# BMS-Shield_rev3.net
KiCad netlist of a schematic drawn in EAGLE
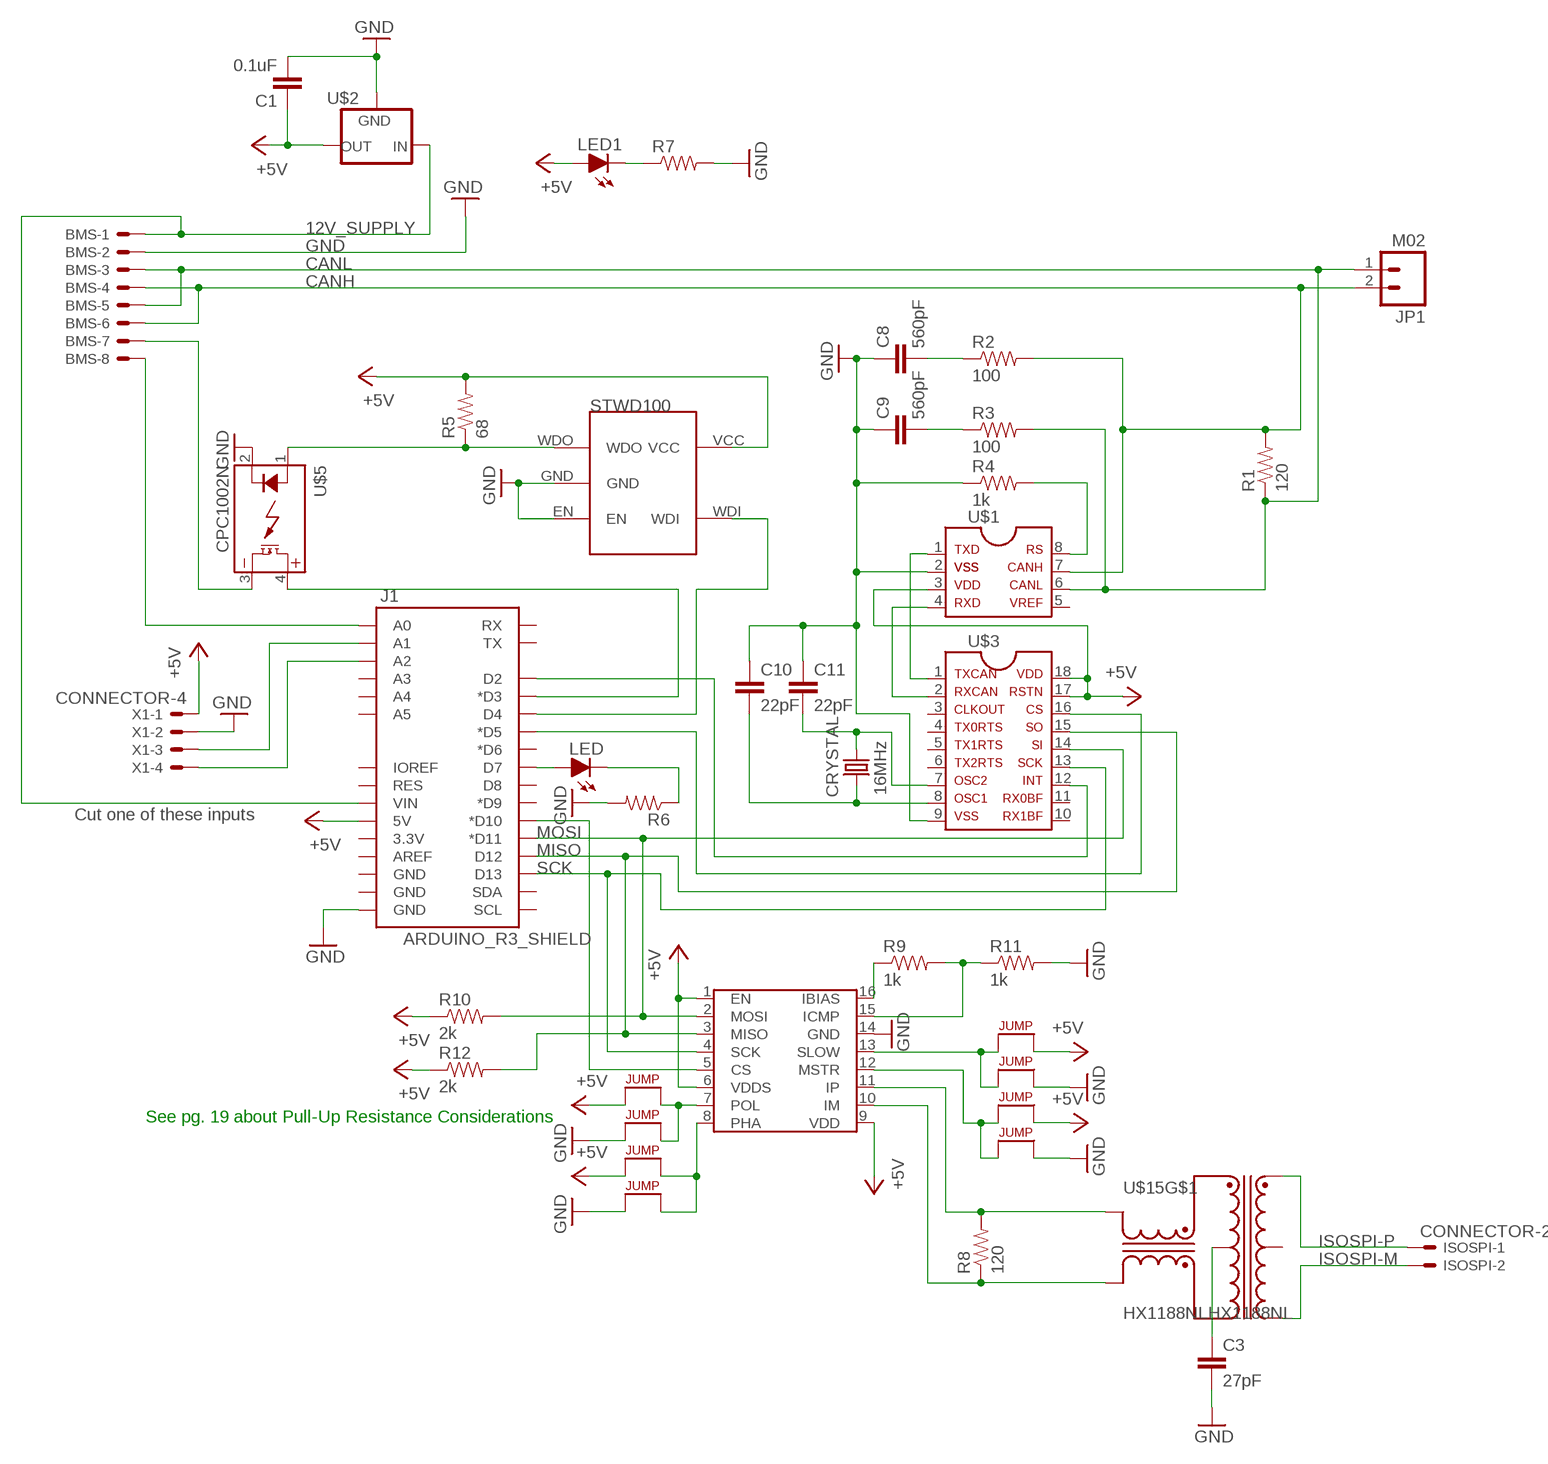
[diagram p0: schematic, sheet 1]

(export (version "E")
  (design (tool "Eeschema 10.0.6"))
  (components
    (comp (ref "BMS")
      (value "MINIFIT_5566-8")
      (footprint "eagle-import:MINIFIT_5566-8")
      (libsource (lib "eagle-import") (part "MINIFIT_5566-8"))
    )
    (comp (ref "C1")
      (value "0.1uF")
      (footprint "eagle-import:0805")
      (libsource (lib "eagle-import") (part "CAP0805"))
    )
    (comp (ref "C3")
      (value "27pF")
      (footprint "eagle-import:0805")
      (libsource (lib "eagle-import") (part "CAP0805"))
    )
    (comp (ref "C8")
      (value "560pF")
      (footprint "eagle-import:0805")
      (libsource (lib "eagle-import") (part "CAP0805"))
    )
    (comp (ref "C9")
      (value "560pF")
      (footprint "eagle-import:0805")
      (libsource (lib "eagle-import") (part "CAP0805"))
    )
    (comp (ref "C10")
      (value "22pF")
      (footprint "eagle-import:0805")
      (libsource (lib "eagle-import") (part "CAP0805"))
    )
    (comp (ref "C11")
      (value "22pF")
      (footprint "eagle-import:0805")
      (libsource (lib "eagle-import") (part "CAP0805"))
    )
    (comp (ref "CRYSTAL")
      (value "16MHz")
      (footprint "eagle-import:HC49UP")
      (libsource (lib "eagle-import") (part "CRYSTALSMD"))
    )
    (comp (ref "ISOSPI")
      (value "CONNECTOR-2")
      (footprint "eagle-import:MINIFIT_5566-2")
      (libsource (lib "eagle-import") (part "CONNECTOR-2"))
    )
    (comp (ref "J1")
      (value "ARDUINO_R3_SHIELD")
      (footprint "eagle-import:UNO_R3_SHIELD")
      (libsource (lib "eagle-import") (part "ARDUINO_R3_SHIELD"))
    )
    (comp (ref "JP1")
      (value "M02")
      (footprint "eagle-import:1X02")
      (libsource (lib "eagle-import") (part "M02"))
    )
    (comp (ref "LED")
      (value "LED-0805")
      (footprint "eagle-import:LED-805")
      (libsource (lib "eagle-import") (part "LED-0805"))
    )
    (comp (ref "LED1")
      (value "LED-0805")
      (footprint "eagle-import:LED-805")
      (libsource (lib "eagle-import") (part "LED-0805"))
    )
    (comp (ref "R1")
      (value "120")
      (footprint "eagle-import:0805")
      (libsource (lib "eagle-import") (part "RESISTOR0805-RES"))
    )
    (comp (ref "R2")
      (value "100")
      (footprint "eagle-import:0805")
      (libsource (lib "eagle-import") (part "RESISTOR0805-RES"))
    )
    (comp (ref "R3")
      (value "100")
      (footprint "eagle-import:0805")
      (libsource (lib "eagle-import") (part "RESISTOR0805-RES"))
    )
    (comp (ref "R4")
      (value "1k")
      (footprint "eagle-import:0805")
      (libsource (lib "eagle-import") (part "RESISTOR0805-RES"))
    )
    (comp (ref "R5")
      (value "68")
      (footprint "eagle-import:0805")
      (libsource (lib "eagle-import") (part "RESISTOR0805-RES"))
    )
    (comp (ref "R6")
      (value "RESISTOR0805-RES")
      (footprint "eagle-import:0805")
      (libsource (lib "eagle-import") (part "RESISTOR0805-RES"))
    )
    (comp (ref "R7")
      (value "RESISTOR0805-RES")
      (footprint "eagle-import:0805")
      (libsource (lib "eagle-import") (part "RESISTOR0805-RES"))
    )
    (comp (ref "R8")
      (value "120")
      (footprint "eagle-import:0805")
      (libsource (lib "eagle-import") (part "RESISTOR0805-RES"))
    )
    (comp (ref "R9")
      (value "1k")
      (footprint "eagle-import:0805")
      (libsource (lib "eagle-import") (part "RESISTOR0805-RES"))
    )
    (comp (ref "R10")
      (value "2k")
      (footprint "eagle-import:0805")
      (libsource (lib "eagle-import") (part "RESISTOR0805-RES"))
    )
    (comp (ref "R11")
      (value "1k")
      (footprint "eagle-import:0805")
      (libsource (lib "eagle-import") (part "RESISTOR0805-RES"))
    )
    (comp (ref "R12")
      (value "2k")
      (footprint "eagle-import:0805")
      (libsource (lib "eagle-import") (part "RESISTOR0805-RES"))
    )
    (comp (ref "U$1")
      (value "MCP2551")
      (footprint "eagle-import:SOIC-08")
      (libsource (lib "eagle-import") (part "MCP2551"))
    )
    (comp (ref "U$2")
      (value "5VREG_LM340-NLM340MPX-5.0/NOPB")
      (footprint "eagle-import:SOT223")
      (libsource (lib "eagle-import") (part "5VREG_LM340-NLM340MPX-5.0/NOPB"))
    )
    (comp (ref "U$3")
      (value "MCP2515SMD")
      (footprint "eagle-import:SOIC-18W")
      (libsource (lib "eagle-import") (part "MCP2515SMD"))
    )
    (comp (ref "U$4")
      (value "STWD100")
      (footprint "eagle-import:SOT23-5")
      (libsource (lib "eagle-import") (part "STWD100"))
    )
    (comp (ref "U$5")
      (value "CPC1002N")
      (footprint "eagle-import:SOP04")
      (libsource (lib "eagle-import") (part "CPC1002N"))
    )
    (comp (ref "U$6")
      (value "LTC6820")
      (footprint "eagle-import:MSOP-16")
      (libsource (lib "eagle-import") (part "LTC6820"))
    )
    (comp (ref "U$7")
      (value "JUMPER")
      (footprint "eagle-import:0805")
      (libsource (lib "eagle-import") (part "JUMPER"))
    )
    (comp (ref "U$8")
      (value "JUMPER")
      (footprint "eagle-import:0805")
      (libsource (lib "eagle-import") (part "JUMPER"))
    )
    (comp (ref "U$9")
      (value "JUMPER")
      (footprint "eagle-import:0805")
      (libsource (lib "eagle-import") (part "JUMPER"))
    )
    (comp (ref "U$10")
      (value "JUMPER")
      (footprint "eagle-import:0805")
      (libsource (lib "eagle-import") (part "JUMPER"))
    )
    (comp (ref "U$11")
      (value "JUMPER")
      (footprint "eagle-import:0805")
      (libsource (lib "eagle-import") (part "JUMPER"))
    )
    (comp (ref "U$12")
      (value "JUMPER")
      (footprint "eagle-import:0805")
      (libsource (lib "eagle-import") (part "JUMPER"))
    )
    (comp (ref "U$13")
      (value "JUMPER")
      (footprint "eagle-import:0805")
      (libsource (lib "eagle-import") (part "JUMPER"))
    )
    (comp (ref "U$14")
      (value "JUMPER")
      (footprint "eagle-import:0805")
      (libsource (lib "eagle-import") (part "JUMPER"))
    )
    (comp (ref "U$15")
      (value "HX1188NLHX1188NL")
      (footprint "eagle-import:HX1188NL")
      (libsource (lib "eagle-import") (part "HX1188NLHX1188NL"))
    )
    (comp (ref "X1")
      (value "CONNECTOR-4")
      (footprint "eagle-import:MINIFIT_5566-4")
      (libsource (lib "eagle-import") (part "CONNECTOR-4"))
    )
  )
  (nets
    (net (code "1") (name "+5V") (class "Default")
      (node (ref "C1") (pin "1") (pinfunction "1_1") (pintype "passive"))
      (node (ref "J1") (pin "5V") (pinfunction "5V_5V") (pintype "bidirectional"))
      (node (ref "LED1") (pin "A") (pinfunction "A_A") (pintype "passive"))
      (node (ref "R10") (pin "1") (pinfunction "1_1") (pintype "passive"))
      (node (ref "R12") (pin "1") (pinfunction "1_1") (pintype "passive"))
      (node (ref "R5") (pin "2") (pinfunction "2_2") (pintype "passive"))
      (node (ref "U$1") (pin "3") (pinfunction "3_3") (pintype "passive"))
      (node (ref "U$10") (pin "1") (pinfunction "P$1_1") (pintype "bidirectional"))
      (node (ref "U$11") (pin "2") (pinfunction "P$2_2") (pintype "bidirectional"))
      (node (ref "U$13") (pin "2") (pinfunction "P$2_2") (pintype "bidirectional"))
      (node (ref "U$2") (pin "3") (pinfunction "OUT_3") (pintype "output"))
      (node (ref "U$3") (pin "17") (pinfunction "17_17") (pintype "passive"))
      (node (ref "U$3") (pin "18") (pinfunction "18_18") (pintype "passive"))
      (node (ref "U$4") (pin "VCC") (pinfunction "VCC_VCC") (pintype "bidirectional"))
      (node (ref "U$6") (pin "1") (pinfunction "EN_1") (pintype "bidirectional"))
      (node (ref "U$6") (pin "6") (pinfunction "VDDS_6") (pintype "bidirectional"))
      (node (ref "U$6") (pin "9") (pinfunction "VDD_9") (pintype "bidirectional"))
      (node (ref "U$7") (pin "1") (pinfunction "P$1_1") (pintype "bidirectional"))
      (node (ref "X1") (pin "1") (pinfunction "S_1") (pintype "passive"))
    )
    (net (code "2") (name "/12V_SUPPLY") (class "Default")
      (node (ref "BMS") (pin "1") (pinfunction "S_1") (pintype "passive"))
      (node (ref "J1") (pin "VIN") (pinfunction "VIN_VIN") (pintype "bidirectional"))
      (node (ref "U$2") (pin "1") (pinfunction "IN_1") (pintype "input"))
    )
    (net (code "3") (name "/CANH") (class "Default")
      (node (ref "BMS") (pin "4") (pinfunction "S_4") (pintype "passive"))
      (node (ref "BMS") (pin "6") (pinfunction "S_6") (pintype "passive"))
      (node (ref "JP1") (pin "2") (pinfunction "2_2") (pintype "passive"))
      (node (ref "R1") (pin "2") (pinfunction "2_2") (pintype "passive"))
      (node (ref "R2") (pin "2") (pinfunction "2_2") (pintype "passive"))
      (node (ref "U$1") (pin "7") (pinfunction "7_7") (pintype "passive"))
    )
    (net (code "4") (name "/CANL") (class "Default")
      (node (ref "BMS") (pin "3") (pinfunction "S_3") (pintype "passive"))
      (node (ref "BMS") (pin "5") (pinfunction "S_5") (pintype "passive"))
      (node (ref "JP1") (pin "1") (pinfunction "1_1") (pintype "passive"))
      (node (ref "R1") (pin "1") (pinfunction "1_1") (pintype "passive"))
      (node (ref "R3") (pin "2") (pinfunction "2_2") (pintype "passive"))
      (node (ref "U$1") (pin "6") (pinfunction "6_6") (pintype "passive"))
    )
    (net (code "5") (name "/ISOSPI-M") (class "Default")
      (node (ref "ISOSPI") (pin "2") (pinfunction "S_2") (pintype "passive"))
      (node (ref "U$15") (pin "3") (pinfunction "D-_3") (pintype "passive"))
    )
    (net (code "6") (name "/ISOSPI-P") (class "Default")
      (node (ref "ISOSPI") (pin "1") (pinfunction "S_1") (pintype "passive"))
      (node (ref "U$15") (pin "1") (pinfunction "D+_1") (pintype "passive"))
    )
    (net (code "7") (name "/MISO") (class "Default")
      (node (ref "J1") (pin "D12") (pinfunction "D12_D12") (pintype "bidirectional"))
      (node (ref "R12") (pin "2") (pinfunction "2_2") (pintype "passive"))
      (node (ref "U$3") (pin "15") (pinfunction "15_15") (pintype "passive"))
      (node (ref "U$6") (pin "3") (pinfunction "MISO_3") (pintype "bidirectional"))
    )
    (net (code "8") (name "/MOSI") (class "Default")
      (node (ref "J1") (pin "D11") (pinfunction "*D11_D11") (pintype "bidirectional"))
      (node (ref "R10") (pin "2") (pinfunction "2_2") (pintype "passive"))
      (node (ref "U$3") (pin "14") (pinfunction "14_14") (pintype "passive"))
      (node (ref "U$6") (pin "2") (pinfunction "MOSI_2") (pintype "bidirectional"))
    )
    (net (code "9") (name "/SCK") (class "Default")
      (node (ref "J1") (pin "D13") (pinfunction "D13_D13") (pintype "bidirectional"))
      (node (ref "U$3") (pin "13") (pinfunction "13_13") (pintype "passive"))
      (node (ref "U$6") (pin "4") (pinfunction "SCK_4") (pintype "bidirectional"))
    )
    (net (code "10") (name "GND") (class "Default")
      (node (ref "BMS") (pin "2") (pinfunction "S_2") (pintype "passive"))
      (node (ref "C1") (pin "2") (pinfunction "2_2") (pintype "passive"))
      (node (ref "C10") (pin "1") (pinfunction "1_1") (pintype "passive"))
      (node (ref "C11") (pin "1") (pinfunction "1_1") (pintype "passive"))
      (node (ref "C3") (pin "2") (pinfunction "2_2") (pintype "passive"))
      (node (ref "C8") (pin "1") (pinfunction "1_1") (pintype "passive"))
      (node (ref "C9") (pin "1") (pinfunction "1_1") (pintype "passive"))
      (node (ref "J1") (pin "GND@0") (pinfunction "GND_GND@0") (pintype "bidirectional"))
      (node (ref "R11") (pin "2") (pinfunction "2_2") (pintype "passive"))
      (node (ref "R4") (pin "1") (pinfunction "1_1") (pintype "passive"))
      (node (ref "R6") (pin "2") (pinfunction "2_2") (pintype "passive"))
      (node (ref "R7") (pin "2") (pinfunction "2_2") (pintype "passive"))
      (node (ref "U$1") (pin "2") (pinfunction "2_2") (pintype "passive"))
      (node (ref "U$12") (pin "2") (pinfunction "P$2_2") (pintype "bidirectional"))
      (node (ref "U$14") (pin "2") (pinfunction "P$2_2") (pintype "bidirectional"))
      (node (ref "U$2") (pin "2") (pinfunction "GND_2") (pintype "input"))
      (node (ref "U$2") (pin "4") (pinfunction "GND_4") (pintype "input"))
      (node (ref "U$3") (pin "9") (pinfunction "9_9") (pintype "passive"))
      (node (ref "U$4") (pin "EN") (pinfunction "EN_EN") (pintype "bidirectional"))
      (node (ref "U$4") (pin "GND") (pinfunction "GND_GND") (pintype "bidirectional"))
      (node (ref "U$5") (pin "2") (pinfunction "CONTROL-_2") (pintype "passive"))
      (node (ref "U$6") (pin "14") (pinfunction "GND_14") (pintype "bidirectional"))
      (node (ref "U$8") (pin "1") (pinfunction "P$1_1") (pintype "bidirectional"))
      (node (ref "U$9") (pin "1") (pinfunction "P$1_1") (pintype "bidirectional"))
      (node (ref "X1") (pin "2") (pinfunction "S_2") (pintype "passive"))
    )
    (net (code "11") (name "Net-(BMSG-S)") (class "Default")
      (node (ref "BMS") (pin "7") (pinfunction "S_7") (pintype "passive"))
      (node (ref "U$5") (pin "3") (pinfunction "DC-_3") (pintype "passive"))
    )
    (net (code "12") (name "Net-(BMSH-S)") (class "Default")
      (node (ref "BMS") (pin "8") (pinfunction "S_8") (pintype "passive"))
      (node (ref "J1") (pin "A0") (pinfunction "A0_A0") (pintype "bidirectional"))
    )
    (net (code "13") (name "Net-(C8-Pad2)") (class "Default")
      (node (ref "C8") (pin "2") (pinfunction "2_2") (pintype "passive"))
      (node (ref "R2") (pin "1") (pinfunction "1_1") (pintype "passive"))
    )
    (net (code "14") (name "Net-(C9-Pad2)") (class "Default")
      (node (ref "C9") (pin "2") (pinfunction "2_2") (pintype "passive"))
      (node (ref "R3") (pin "1") (pinfunction "1_1") (pintype "passive"))
    )
    (net (code "15") (name "Net-(C10-Pad2)") (class "Default")
      (node (ref "C10") (pin "2") (pinfunction "2_2") (pintype "passive"))
      (node (ref "CRYSTAL") (pin "2") (pinfunction "2_2") (pintype "passive"))
      (node (ref "U$3") (pin "8") (pinfunction "8_8") (pintype "passive"))
    )
    (net (code "16") (name "Net-(C11-Pad2)") (class "Default")
      (node (ref "C11") (pin "2") (pinfunction "2_2") (pintype "passive"))
      (node (ref "CRYSTAL") (pin "1") (pinfunction "1_1") (pintype "passive"))
      (node (ref "U$3") (pin "7") (pinfunction "7_7") (pintype "passive"))
    )
    (net (code "17") (name "Net-(J1-*D3)") (class "Default")
      (node (ref "J1") (pin "D3") (pinfunction "*D3_D3") (pintype "bidirectional"))
      (node (ref "U$5") (pin "4") (pinfunction "DC+_4") (pintype "passive"))
    )
    (net (code "18") (name "Net-(J1-*D5)") (class "Default")
      (node (ref "J1") (pin "D5") (pinfunction "*D5_D5") (pintype "bidirectional"))
      (node (ref "U$3") (pin "16") (pinfunction "16_16") (pintype "passive"))
    )
    (net (code "19") (name "Net-(J1-*D10)") (class "Default")
      (node (ref "J1") (pin "D10") (pinfunction "*D10_D10") (pintype "bidirectional"))
      (node (ref "U$6") (pin "5") (pinfunction "CS_5") (pintype "bidirectional"))
    )
    (net (code "20") (name "Net-(J1-PadD2)") (class "Default")
      (node (ref "J1") (pin "D2") (pinfunction "D2_D2") (pintype "bidirectional"))
      (node (ref "U$3") (pin "12") (pinfunction "12_12") (pintype "passive"))
    )
    (net (code "21") (name "Net-(J1-PadD4)") (class "Default")
      (node (ref "J1") (pin "D4") (pinfunction "D4_D4") (pintype "bidirectional"))
      (node (ref "U$4") (pin "WDI") (pinfunction "WDI_WDI") (pintype "bidirectional"))
    )
    (net (code "22") (name "Net-(J1-PadD7)") (class "Default")
      (node (ref "J1") (pin "D7") (pinfunction "D7_D7") (pintype "bidirectional"))
      (node (ref "LED") (pin "A") (pinfunction "A_A") (pintype "passive"))
    )
    (net (code "23") (name "Net-(LED-PadC)") (class "Default")
      (node (ref "LED") (pin "C") (pinfunction "C_C") (pintype "passive"))
      (node (ref "R6") (pin "1") (pinfunction "1_1") (pintype "passive"))
    )
    (net (code "24") (name "Net-(LED1-PadC)") (class "Default")
      (node (ref "LED1") (pin "C") (pinfunction "C_C") (pintype "passive"))
      (node (ref "R7") (pin "1") (pinfunction "1_1") (pintype "passive"))
    )
    (net (code "25") (name "Net-(R4-Pad2)") (class "Default")
      (node (ref "R4") (pin "2") (pinfunction "2_2") (pintype "passive"))
      (node (ref "U$1") (pin "8") (pinfunction "8_8") (pintype "passive"))
    )
    (net (code "26") (name "Net-(U$1-Pad1)") (class "Default")
      (node (ref "U$1") (pin "1") (pinfunction "1_1") (pintype "passive"))
      (node (ref "U$3") (pin "1") (pinfunction "1_1") (pintype "passive"))
    )
    (net (code "27") (name "Net-(U$1-Pad4)") (class "Default")
      (node (ref "U$1") (pin "4") (pinfunction "4_4") (pintype "passive"))
      (node (ref "U$3") (pin "2") (pinfunction "2_2") (pintype "passive"))
    )
    (net (code "28") (name "Net-(U$5-CONTROL+)") (class "Default")
      (node (ref "R5") (pin "1") (pinfunction "1_1") (pintype "passive"))
      (node (ref "U$4") (pin "WDO") (pinfunction "WDO_WDO") (pintype "bidirectional"))
      (node (ref "U$5") (pin "1") (pinfunction "CONTROL+_1") (pintype "passive"))
    )
    (net (code "29") (name "Net-(U$6-IBIAS)") (class "Default")
      (node (ref "R9") (pin "1") (pinfunction "1_1") (pintype "passive"))
      (node (ref "U$6") (pin "16") (pinfunction "IBIAS_16") (pintype "bidirectional"))
    )
    (net (code "30") (name "Net-(U$6-ICMP)") (class "Default")
      (node (ref "R11") (pin "1") (pinfunction "1_1") (pintype "passive"))
      (node (ref "R9") (pin "2") (pinfunction "2_2") (pintype "passive"))
      (node (ref "U$6") (pin "15") (pinfunction "ICMP_15") (pintype "bidirectional"))
    )
    (net (code "31") (name "Net-(U$6-POL)") (class "Default")
      (node (ref "U$6") (pin "7") (pinfunction "POL_7") (pintype "bidirectional"))
      (node (ref "U$7") (pin "2") (pinfunction "P$2_2") (pintype "bidirectional"))
      (node (ref "U$8") (pin "2") (pinfunction "P$2_2") (pintype "bidirectional"))
    )
    (net (code "32") (name "Net-(U$10-P$2)") (class "Default")
      (node (ref "U$10") (pin "2") (pinfunction "P$2_2") (pintype "bidirectional"))
      (node (ref "U$6") (pin "8") (pinfunction "PHA_8") (pintype "bidirectional"))
      (node (ref "U$9") (pin "2") (pinfunction "P$2_2") (pintype "bidirectional"))
    )
    (net (code "33") (name "Net-(U$11-P$1)") (class "Default")
      (node (ref "U$11") (pin "1") (pinfunction "P$1_1") (pintype "bidirectional"))
      (node (ref "U$12") (pin "1") (pinfunction "P$1_1") (pintype "bidirectional"))
      (node (ref "U$6") (pin "13") (pinfunction "SLOW_13") (pintype "bidirectional"))
    )
    (net (code "34") (name "Net-(U$13-P$1)") (class "Default")
      (node (ref "U$13") (pin "1") (pinfunction "P$1_1") (pintype "bidirectional"))
      (node (ref "U$14") (pin "1") (pinfunction "P$1_1") (pintype "bidirectional"))
      (node (ref "U$6") (pin "12") (pinfunction "MSTR_12") (pintype "bidirectional"))
    )
    (net (code "35") (name "Net-(U$15A-CX)") (class "Default")
      (node (ref "C3") (pin "1") (pinfunction "1_1") (pintype "passive"))
      (node (ref "U$15") (pin "15") (pinfunction "CX_15") (pintype "passive"))
    )
    (net (code "36") (name "Net-(U$15A-X+)") (class "Default")
      (node (ref "R8") (pin "2") (pinfunction "2_2") (pintype "passive"))
      (node (ref "U$15") (pin "16") (pinfunction "X+_16") (pintype "passive"))
      (node (ref "U$6") (pin "11") (pinfunction "IP_11") (pintype "bidirectional"))
    )
    (net (code "37") (name "Net-(U$15A-X-)") (class "Default")
      (node (ref "R8") (pin "1") (pinfunction "1_1") (pintype "passive"))
      (node (ref "U$15") (pin "14") (pinfunction "X-_14") (pintype "passive"))
      (node (ref "U$6") (pin "10") (pinfunction "IM_10") (pintype "bidirectional"))
    )
    (net (code "38") (name "Net-(X1C-S)") (class "Default")
      (node (ref "J1") (pin "A1") (pinfunction "A1_A1") (pintype "bidirectional"))
      (node (ref "X1") (pin "3") (pinfunction "S_3") (pintype "passive"))
    )
    (net (code "39") (name "Net-(X1D-S)") (class "Default")
      (node (ref "J1") (pin "A2") (pinfunction "A2_A2") (pintype "bidirectional"))
      (node (ref "X1") (pin "4") (pinfunction "S_4") (pintype "passive"))
    )
    (net (code "40") (name "unconnected-(J1-*D6-PadD6)") (class "Default")
      (node (ref "J1") (pin "D6") (pinfunction "*D6_D6") (pintype "bidirectional"))
    )
    (net (code "41") (name "unconnected-(J1-*D9-PadD9)") (class "Default")
      (node (ref "J1") (pin "D9") (pinfunction "*D9_D9") (pintype "bidirectional"))
    )
    (net (code "42") (name "unconnected-(J1-GND-PadGND@1)") (class "Default")
      (node (ref "J1") (pin "GND@1") (pinfunction "GND_GND@1") (pintype "bidirectional"))
    )
    (net (code "43") (name "unconnected-(J1-GND-PadGND@2)") (class "Default")
      (node (ref "J1") (pin "GND@2") (pinfunction "GND_GND@2") (pintype "bidirectional"))
    )
    (net (code "44") (name "unconnected-(J1-Pad3.3V)") (class "Default")
      (node (ref "J1") (pin "3.3V") (pinfunction "3.3V_3.3V") (pintype "bidirectional"))
    )
    (net (code "45") (name "unconnected-(J1-PadA3)") (class "Default")
      (node (ref "J1") (pin "A3") (pinfunction "A3_A3") (pintype "bidirectional"))
    )
    (net (code "46") (name "unconnected-(J1-PadA4)") (class "Default")
      (node (ref "J1") (pin "A4") (pinfunction "A4_A4") (pintype "bidirectional"))
    )
    (net (code "47") (name "unconnected-(J1-PadA5)") (class "Default")
      (node (ref "J1") (pin "A5") (pinfunction "A5_A5") (pintype "bidirectional"))
    )
    (net (code "48") (name "unconnected-(J1-PadAREF)") (class "Default")
      (node (ref "J1") (pin "AREF") (pinfunction "AREF_AREF") (pintype "bidirectional"))
    )
    (net (code "49") (name "unconnected-(J1-PadD8)") (class "Default")
      (node (ref "J1") (pin "D8") (pinfunction "D8_D8") (pintype "bidirectional"))
    )
    (net (code "50") (name "unconnected-(J1-PadIOREF)") (class "Default")
      (node (ref "J1") (pin "IOREF") (pinfunction "IOREF_IOREF") (pintype "bidirectional"))
    )
    (net (code "51") (name "unconnected-(J1-PadRES)") (class "Default")
      (node (ref "J1") (pin "RES") (pinfunction "RES_RES") (pintype "bidirectional"))
    )
    (net (code "52") (name "unconnected-(J1-PadRX)") (class "Default")
      (node (ref "J1") (pin "RX") (pinfunction "RX_RX") (pintype "bidirectional"))
    )
    (net (code "53") (name "unconnected-(J1-PadSCL)") (class "Default")
      (node (ref "J1") (pin "SCL") (pinfunction "SCL_SCL") (pintype "bidirectional"))
    )
    (net (code "54") (name "unconnected-(J1-PadSDA)") (class "Default")
      (node (ref "J1") (pin "SDA") (pinfunction "SDA_SDA") (pintype "bidirectional"))
    )
    (net (code "55") (name "unconnected-(J1-PadTX)") (class "Default")
      (node (ref "J1") (pin "TX") (pinfunction "TX_TX") (pintype "bidirectional"))
    )
    (net (code "56") (name "unconnected-(U$1-Pad5)") (class "Default")
      (node (ref "U$1") (pin "5") (pinfunction "5_5") (pintype "passive"))
    )
    (net (code "57") (name "unconnected-(U$3-Pad3)") (class "Default")
      (node (ref "U$3") (pin "3") (pinfunction "3_3") (pintype "passive"))
    )
    (net (code "58") (name "unconnected-(U$3-Pad4)") (class "Default")
      (node (ref "U$3") (pin "4") (pinfunction "4_4") (pintype "passive"))
    )
    (net (code "59") (name "unconnected-(U$3-Pad5)") (class "Default")
      (node (ref "U$3") (pin "5") (pinfunction "5_5") (pintype "passive"))
    )
    (net (code "60") (name "unconnected-(U$3-Pad6)") (class "Default")
      (node (ref "U$3") (pin "6") (pinfunction "6_6") (pintype "passive"))
    )
    (net (code "61") (name "unconnected-(U$3-Pad10)") (class "Default")
      (node (ref "U$3") (pin "10") (pinfunction "10_10") (pintype "passive"))
    )
    (net (code "62") (name "unconnected-(U$3-Pad11)") (class "Default")
      (node (ref "U$3") (pin "11") (pinfunction "11_11") (pintype "passive"))
    )
    (net (code "63") (name "unconnected-(U$15A-CD-Pad2)") (class "Default")
      (node (ref "U$15") (pin "2") (pinfunction "CD_2") (pintype "passive"))
    )
  )
)
